# Type-C.net
KiCad netlist of a schematic drawn in Altium Designer
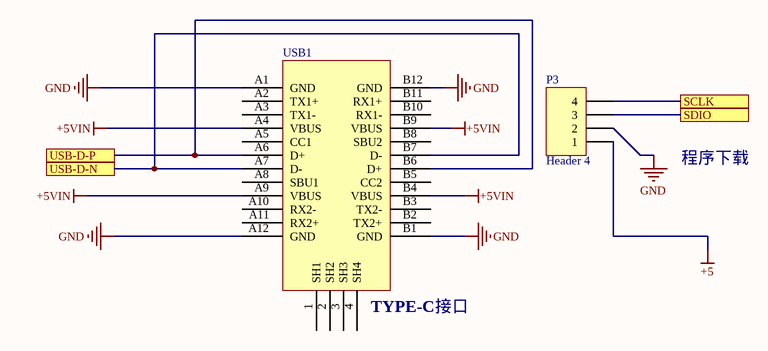
[diagram p0: Type-C接口及程序下载.SchDoc]

(export (version "E")
  (design (tool "Eeschema 10.0.6"))
  (components
    (comp (ref "P3")
      (value "Header 4")
      (footprint "HDR1X4")
      (description "Header, 4-Pin")
      (fields (field (name "PUBLISHER") "Altium Limited"))
      (libsource (lib "基于SMT32的DDS信号源原理图库") (part "Header 4"))
    )
    (comp (ref "USB1")
      (value "TYPE-C")
      (footprint "TYPE-C")
      (libsource (lib "基于SMT32的DDS信号源原理图库") (part "TYPE-C"))
    )
  )
  (nets
    (net (code "1") (name "+5") (class "Default")
      (node (ref "P3") (pin "1") (pinfunction "1_1") (pintype "passive"))
    )
    (net (code "2") (name "+5VIN") (class "Default")
      (node (ref "USB1") (pin "A4") (pinfunction "VBUS_A4") (pintype "passive"))
      (node (ref "USB1") (pin "A9") (pinfunction "VBUS_A9") (pintype "passive"))
      (node (ref "USB1") (pin "B4") (pinfunction "VBUS_B4") (pintype "passive"))
      (node (ref "USB1") (pin "B9") (pinfunction "VBUS_B9") (pintype "passive"))
    )
    (net (code "3") (name "/SCLK") (class "Default")
      (node (ref "P3") (pin "4") (pinfunction "4_4") (pintype "passive"))
    )
    (net (code "4") (name "/SDIO") (class "Default")
      (node (ref "P3") (pin "3") (pinfunction "3_3") (pintype "passive"))
    )
    (net (code "5") (name "/USB-D-N") (class "Default")
      (node (ref "USB1") (pin "A7") (pinfunction "D-_A7") (pintype "passive"))
      (node (ref "USB1") (pin "B7") (pinfunction "D-_B7") (pintype "passive"))
    )
    (net (code "6") (name "/USB-D-P") (class "Default")
      (node (ref "USB1") (pin "A6") (pinfunction "D+_A6") (pintype "passive"))
      (node (ref "USB1") (pin "B6") (pinfunction "D+_B6") (pintype "passive"))
    )
    (net (code "7") (name "GND") (class "Default")
      (node (ref "P3") (pin "2") (pinfunction "2_2") (pintype "passive"))
      (node (ref "USB1") (pin "A1") (pinfunction "GND_A1") (pintype "passive"))
      (node (ref "USB1") (pin "A12") (pinfunction "GND_A12") (pintype "passive"))
      (node (ref "USB1") (pin "B1") (pinfunction "GND_B1") (pintype "passive"))
      (node (ref "USB1") (pin "B12") (pinfunction "GND_B12") (pintype "passive"))
    )
    (net (code "8") (name "unconnected-(USB1-CC1-PadA5)") (class "Default")
      (node (ref "USB1") (pin "A5") (pinfunction "CC1_A5") (pintype "passive"))
    )
    (net (code "9") (name "unconnected-(USB1-CC2-PadB5)") (class "Default")
      (node (ref "USB1") (pin "B5") (pinfunction "CC2_B5") (pintype "passive"))
    )
    (net (code "10") (name "unconnected-(USB1-RX1+-PadB11)") (class "Default")
      (node (ref "USB1") (pin "B11") (pinfunction "RX1+_B11") (pintype "passive"))
    )
    (net (code "11") (name "unconnected-(USB1-RX1--PadB10)") (class "Default")
      (node (ref "USB1") (pin "B10") (pinfunction "RX1-_B10") (pintype "passive"))
    )
    (net (code "12") (name "unconnected-(USB1-RX2+-PadA11)") (class "Default")
      (node (ref "USB1") (pin "A11") (pinfunction "RX2+_A11") (pintype "passive"))
    )
    (net (code "13") (name "unconnected-(USB1-RX2--PadA10)") (class "Default")
      (node (ref "USB1") (pin "A10") (pinfunction "RX2-_A10") (pintype "passive"))
    )
    (net (code "14") (name "unconnected-(USB1-SBU1-PadA8)") (class "Default")
      (node (ref "USB1") (pin "A8") (pinfunction "SBU1_A8") (pintype "passive"))
    )
    (net (code "15") (name "unconnected-(USB1-SBU2-PadB8)") (class "Default")
      (node (ref "USB1") (pin "B8") (pinfunction "SBU2_B8") (pintype "passive"))
    )
    (net (code "16") (name "unconnected-(USB1-SH1-Pad1)") (class "Default")
      (node (ref "USB1") (pin "1") (pinfunction "SH1_1") (pintype "passive"))
    )
    (net (code "17") (name "unconnected-(USB1-SH2-Pad2)") (class "Default")
      (node (ref "USB1") (pin "2") (pinfunction "SH2_2") (pintype "passive"))
    )
    (net (code "18") (name "unconnected-(USB1-SH3-Pad3)") (class "Default")
      (node (ref "USB1") (pin "3") (pinfunction "SH3_3") (pintype "passive"))
    )
    (net (code "19") (name "unconnected-(USB1-SH4-Pad4)") (class "Default")
      (node (ref "USB1") (pin "4") (pinfunction "SH4_4") (pintype "passive"))
    )
    (net (code "20") (name "unconnected-(USB1-TX1+-PadA2)") (class "Default")
      (node (ref "USB1") (pin "A2") (pinfunction "TX1+_A2") (pintype "passive"))
    )
    (net (code "21") (name "unconnected-(USB1-TX1--PadA3)") (class "Default")
      (node (ref "USB1") (pin "A3") (pinfunction "TX1-_A3") (pintype "passive"))
    )
    (net (code "22") (name "unconnected-(USB1-TX2+-PadB2)") (class "Default")
      (node (ref "USB1") (pin "B2") (pinfunction "TX2+_B2") (pintype "passive"))
    )
    (net (code "23") (name "unconnected-(USB1-TX2--PadB3)") (class "Default")
      (node (ref "USB1") (pin "B3") (pinfunction "TX2-_B3") (pintype "passive"))
    )
  )
)
